# qPCR_pcb_breakout_TLC59281DBQR.net
KiCad netlist of a schematic drawn in EAGLE
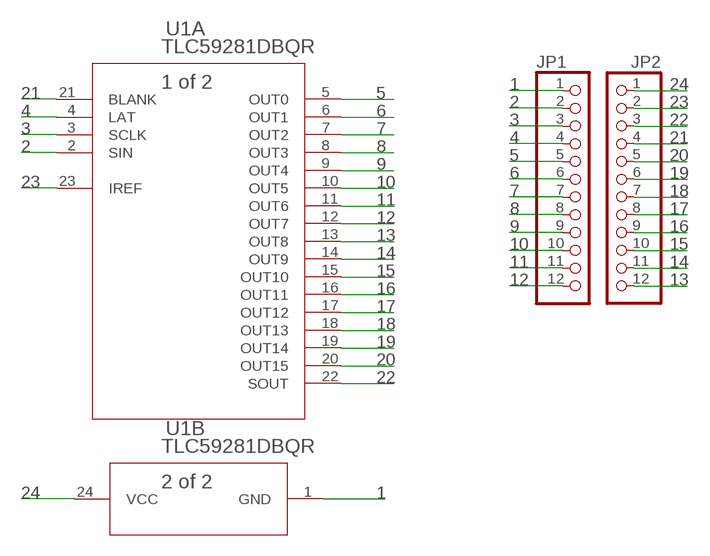
[diagram p0: schematic, sheet 1]

(export (version "E")
  (design (tool "Eeschema 10.0.6"))
  (components
    (comp (ref "JP1")
      (value "PINHD-1X12")
      (footprint "eagle-import:1X12")
      (libsource (lib "eagle-import") (part "PINHD-1X12"))
    )
    (comp (ref "JP2")
      (value "PINHD-1X12")
      (footprint "eagle-import:1X12")
      (libsource (lib "eagle-import") (part "PINHD-1X12"))
    )
    (comp (ref "U1")
      (value "TLC59281DBQR")
      (footprint "eagle-import:DBQ24")
      (fields (field (name "MANUFACTURER") "Texas Instruments"))
      (libsource (lib "eagle-import") (part "TLC59281DBQR"))
    )
  )
  (nets
    (net (code "1") (name "/1") (class "Default")
      (node (ref "JP1") (pin "1") (pinfunction "1_1") (pintype "passive"))
      (node (ref "U1") (pin "1") (pinfunction "GND_1") (pintype "power_in"))
    )
    (net (code "2") (name "/2") (class "Default")
      (node (ref "JP1") (pin "2") (pinfunction "2_2") (pintype "passive"))
      (node (ref "U1") (pin "2") (pinfunction "SIN_2") (pintype "input"))
    )
    (net (code "3") (name "/3") (class "Default")
      (node (ref "JP1") (pin "3") (pinfunction "3_3") (pintype "passive"))
      (node (ref "U1") (pin "3") (pinfunction "SCLK_3") (pintype "input"))
    )
    (net (code "4") (name "/4") (class "Default")
      (node (ref "JP1") (pin "4") (pinfunction "4_4") (pintype "passive"))
      (node (ref "U1") (pin "4") (pinfunction "LAT_4") (pintype "input"))
    )
    (net (code "5") (name "/5") (class "Default")
      (node (ref "JP1") (pin "5") (pinfunction "5_5") (pintype "passive"))
      (node (ref "U1") (pin "5") (pinfunction "OUT0_5") (pintype "output"))
    )
    (net (code "6") (name "/6") (class "Default")
      (node (ref "JP1") (pin "6") (pinfunction "6_6") (pintype "passive"))
      (node (ref "U1") (pin "6") (pinfunction "OUT1_6") (pintype "output"))
    )
    (net (code "7") (name "/7") (class "Default")
      (node (ref "JP1") (pin "7") (pinfunction "7_7") (pintype "passive"))
      (node (ref "U1") (pin "7") (pinfunction "OUT2_7") (pintype "output"))
    )
    (net (code "8") (name "/8") (class "Default")
      (node (ref "JP1") (pin "8") (pinfunction "8_8") (pintype "passive"))
      (node (ref "U1") (pin "8") (pinfunction "OUT3_8") (pintype "output"))
    )
    (net (code "9") (name "/9") (class "Default")
      (node (ref "JP1") (pin "9") (pinfunction "9_9") (pintype "passive"))
      (node (ref "U1") (pin "9") (pinfunction "OUT4_9") (pintype "output"))
    )
    (net (code "10") (name "/10") (class "Default")
      (node (ref "JP1") (pin "10") (pinfunction "10_10") (pintype "passive"))
      (node (ref "U1") (pin "10") (pinfunction "OUT5_10") (pintype "output"))
    )
    (net (code "11") (name "/11") (class "Default")
      (node (ref "JP1") (pin "11") (pinfunction "11_11") (pintype "passive"))
      (node (ref "U1") (pin "11") (pinfunction "OUT6_11") (pintype "output"))
    )
    (net (code "12") (name "/12") (class "Default")
      (node (ref "JP1") (pin "12") (pinfunction "12_12") (pintype "passive"))
      (node (ref "U1") (pin "12") (pinfunction "OUT7_12") (pintype "output"))
    )
    (net (code "13") (name "/13") (class "Default")
      (node (ref "JP2") (pin "12") (pinfunction "12_12") (pintype "passive"))
      (node (ref "U1") (pin "13") (pinfunction "OUT8_13") (pintype "output"))
    )
    (net (code "14") (name "/14") (class "Default")
      (node (ref "JP2") (pin "11") (pinfunction "11_11") (pintype "passive"))
      (node (ref "U1") (pin "14") (pinfunction "OUT9_14") (pintype "output"))
    )
    (net (code "15") (name "/15") (class "Default")
      (node (ref "JP2") (pin "10") (pinfunction "10_10") (pintype "passive"))
      (node (ref "U1") (pin "15") (pinfunction "OUT10_15") (pintype "output"))
    )
    (net (code "16") (name "/16") (class "Default")
      (node (ref "JP2") (pin "9") (pinfunction "9_9") (pintype "passive"))
      (node (ref "U1") (pin "16") (pinfunction "OUT11_16") (pintype "output"))
    )
    (net (code "17") (name "/17") (class "Default")
      (node (ref "JP2") (pin "8") (pinfunction "8_8") (pintype "passive"))
      (node (ref "U1") (pin "17") (pinfunction "OUT12_17") (pintype "output"))
    )
    (net (code "18") (name "/18") (class "Default")
      (node (ref "JP2") (pin "7") (pinfunction "7_7") (pintype "passive"))
      (node (ref "U1") (pin "18") (pinfunction "OUT13_18") (pintype "output"))
    )
    (net (code "19") (name "/19") (class "Default")
      (node (ref "JP2") (pin "6") (pinfunction "6_6") (pintype "passive"))
      (node (ref "U1") (pin "19") (pinfunction "OUT14_19") (pintype "output"))
    )
    (net (code "20") (name "/20") (class "Default")
      (node (ref "JP2") (pin "5") (pinfunction "5_5") (pintype "passive"))
      (node (ref "U1") (pin "20") (pinfunction "OUT15_20") (pintype "output"))
    )
    (net (code "21") (name "/21") (class "Default")
      (node (ref "JP2") (pin "4") (pinfunction "4_4") (pintype "passive"))
      (node (ref "U1") (pin "21") (pinfunction "BLANK_21") (pintype "input"))
    )
    (net (code "22") (name "/22") (class "Default")
      (node (ref "JP2") (pin "3") (pinfunction "3_3") (pintype "passive"))
      (node (ref "U1") (pin "22") (pinfunction "SOUT_22") (pintype "output"))
    )
    (net (code "23") (name "/23") (class "Default")
      (node (ref "JP2") (pin "2") (pinfunction "2_2") (pintype "passive"))
      (node (ref "U1") (pin "23") (pinfunction "IREF_23") (pintype "bidirectional"))
    )
    (net (code "24") (name "/24") (class "Default")
      (node (ref "JP2") (pin "1") (pinfunction "1_1") (pintype "passive"))
      (node (ref "U1") (pin "24") (pinfunction "VCC_24") (pintype "power_in"))
    )
  )
)
